# CarPC-CC-Var2.net
KiCad netlist of a schematic drawn in EAGLE
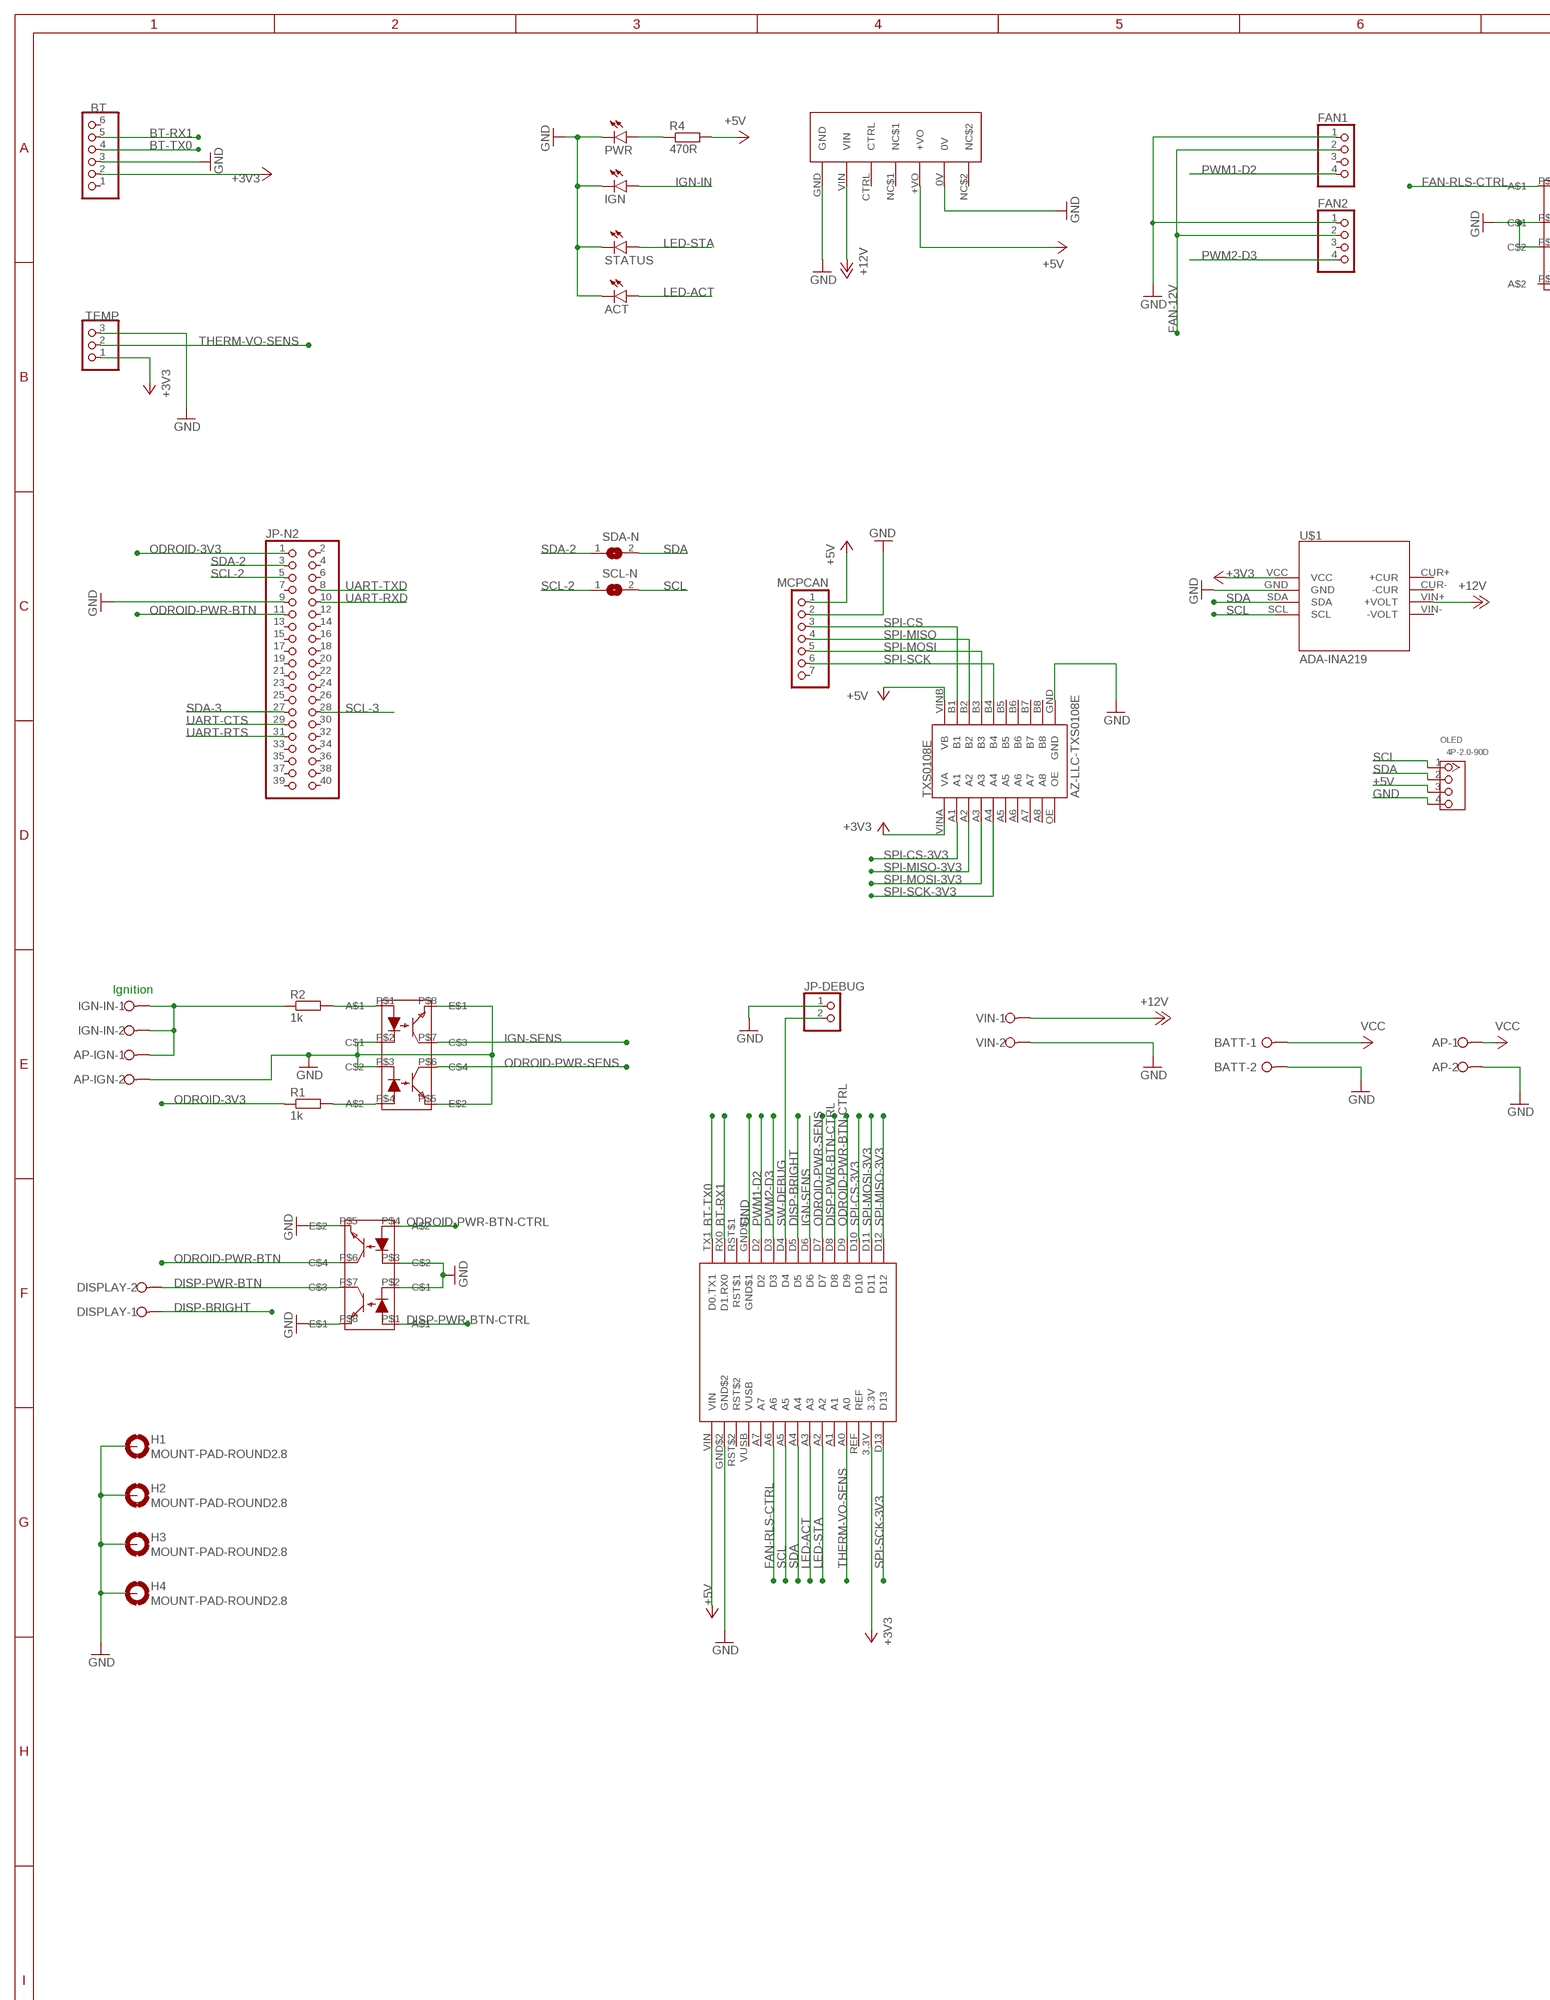
[diagram p0: schematic, sheet 1, part 1 of 2]
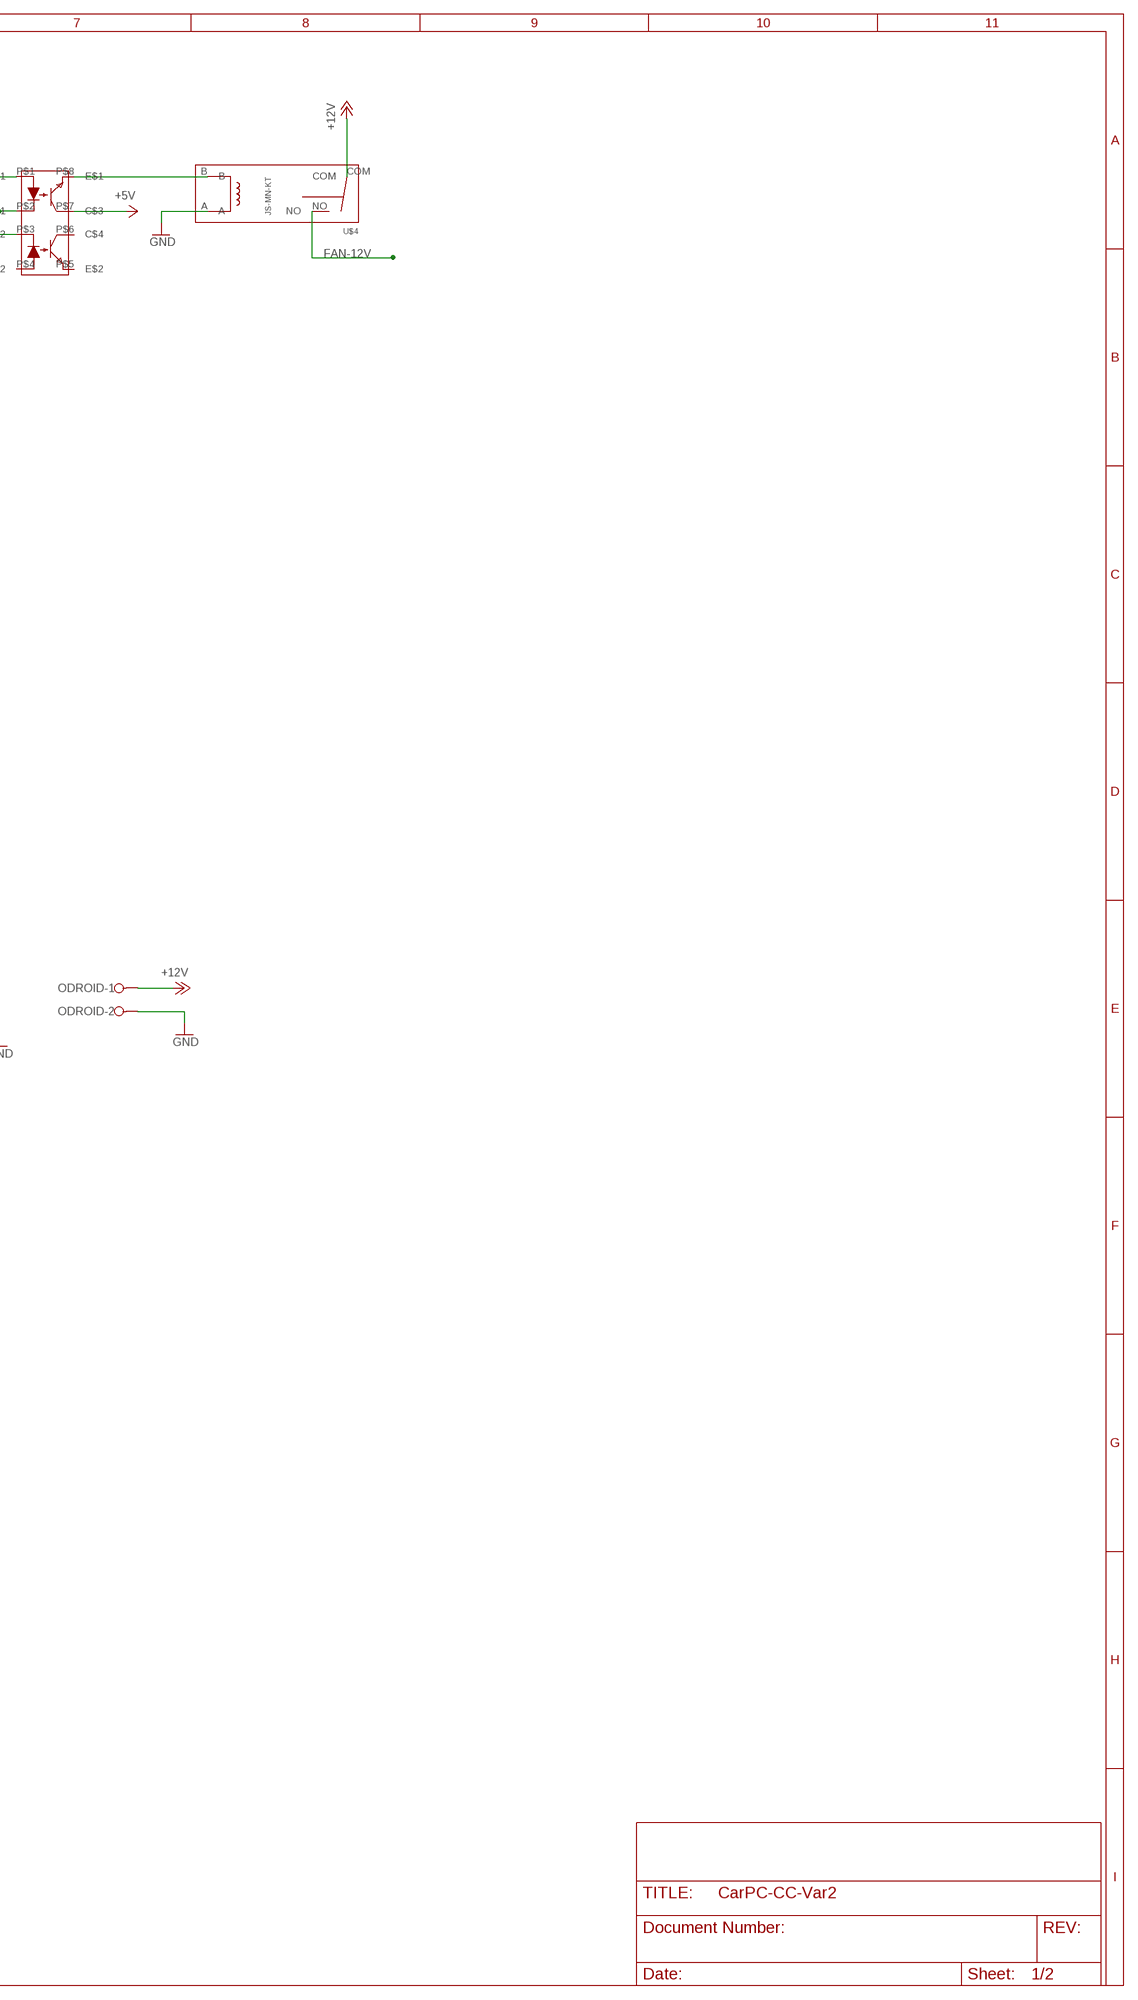
[diagram p1: schematic, sheet 1, part 2 of 2]

(export (version "E")
  (design (tool "Eeschema 10.0.6"))
  (components
    (comp (ref "ACT")
      (value "LED3MM")
      (footprint "eagle-import:LED3MM")
      (libsource (lib "eagle-import") (part "LED3MM"))
    )
    (comp (ref "AP")
      (value "W237-02P")
      (footprint "eagle-import:W237-132")
      (libsource (lib "eagle-import") (part "W237-02P"))
    )
    (comp (ref "AP-IGN")
      (value "W237-02P")
      (footprint "eagle-import:W237-132")
      (libsource (lib "eagle-import") (part "W237-02P"))
    )
    (comp (ref "ARD-NANO-33-IOT")
      (value "ARDUINONANO33IOT")
      (footprint "eagle-import:FPR_ARDNANO33IOT")
      (libsource (lib "eagle-import") (part "ARDUINONANO33IOT"))
    )
    (comp (ref "BATT")
      (value "W237-02P")
      (footprint "eagle-import:W237-132")
      (libsource (lib "eagle-import") (part "W237-02P"))
    )
    (comp (ref "BT")
      (value "PINHD-1X6/90")
      (footprint "eagle-import:1X06_90")
      (libsource (lib "eagle-import") (part "PINHD-1X6/90"))
    )
    (comp (ref "DISPLAY")
      (value "W237-02P")
      (footprint "eagle-import:W237-132")
      (libsource (lib "eagle-import") (part "W237-02P"))
    )
    (comp (ref "FAN1")
      (value "PINHD-1X4")
      (footprint "eagle-import:1X04")
      (libsource (lib "eagle-import") (part "PINHD-1X4"))
    )
    (comp (ref "FAN2")
      (value "PINHD-1X4")
      (footprint "eagle-import:1X04")
      (libsource (lib "eagle-import") (part "PINHD-1X4"))
    )
    (comp (ref "H1")
      (value "MOUNT-PAD-ROUND2.8")
      (footprint "eagle-import:2,8-PAD")
      (libsource (lib "eagle-import") (part "MOUNT-PAD-ROUND2.8"))
    )
    (comp (ref "H2")
      (value "MOUNT-PAD-ROUND2.8")
      (footprint "eagle-import:2,8-PAD")
      (libsource (lib "eagle-import") (part "MOUNT-PAD-ROUND2.8"))
    )
    (comp (ref "H3")
      (value "MOUNT-PAD-ROUND2.8")
      (footprint "eagle-import:2,8-PAD")
      (libsource (lib "eagle-import") (part "MOUNT-PAD-ROUND2.8"))
    )
    (comp (ref "H4")
      (value "MOUNT-PAD-ROUND2.8")
      (footprint "eagle-import:2,8-PAD")
      (libsource (lib "eagle-import") (part "MOUNT-PAD-ROUND2.8"))
    )
    (comp (ref "IGN")
      (value "LED3MM")
      (footprint "eagle-import:LED3MM")
      (libsource (lib "eagle-import") (part "LED3MM"))
    )
    (comp (ref "IGN-IN")
      (value "W237-02P")
      (footprint "eagle-import:W237-132")
      (libsource (lib "eagle-import") (part "W237-02P"))
    )
    (comp (ref "JP-DEBUG")
      (value "PINHD-1X2")
      (footprint "eagle-import:1X02")
      (libsource (lib "eagle-import") (part "PINHD-1X2"))
    )
    (comp (ref "JP-N2")
      (value "PINHD-2X20")
      (footprint "eagle-import:2X20")
      (libsource (lib "eagle-import") (part "PINHD-2X20"))
    )
    (comp (ref "MCPCAN")
      (value "PINHD-1X7/90")
      (footprint "eagle-import:1X07_90")
      (libsource (lib "eagle-import") (part "PINHD-1X7/90"))
    )
    (comp (ref "ODROID")
      (value "W237-02P")
      (footprint "eagle-import:W237-132")
      (libsource (lib "eagle-import") (part "W237-02P"))
    )
    (comp (ref "OK-FAN-CTRL")
      (value "ILD74")
      (footprint "eagle-import:FPR_ILD74")
      (libsource (lib "eagle-import") (part "ILD74"))
    )
    (comp (ref "OK-PWR-IGN")
      (value "ILD74")
      (footprint "eagle-import:FPR_ILD74")
      (libsource (lib "eagle-import") (part "ILD74"))
    )
    (comp (ref "OK-PWR-N2_DISP")
      (value "ILD74")
      (footprint "eagle-import:FPR_ILD74")
      (libsource (lib "eagle-import") (part "ILD74"))
    )
    (comp (ref "OLED")
      (value "4P-2.0-90D")
      (footprint "eagle-import:HW4-2.0-90D")
      (libsource (lib "eagle-import") (part "GROVE-CONNECTOR-DIP-90D(4P-2.0)"))
    )
    (comp (ref "PWR")
      (value "LED3MM")
      (footprint "eagle-import:LED3MM")
      (libsource (lib "eagle-import") (part "LED3MM"))
    )
    (comp (ref "R1")
      (value "1k")
      (footprint "eagle-import:0204_7")
      (libsource (lib "eagle-import") (part "R-EU_0204/7"))
    )
    (comp (ref "R2")
      (value "1k")
      (footprint "eagle-import:0204_7")
      (libsource (lib "eagle-import") (part "R-EU_0204/7"))
    )
    (comp (ref "R4")
      (value "470R")
      (footprint "eagle-import:0204_7")
      (libsource (lib "eagle-import") (part "R-EU_0204/7"))
    )
    (comp (ref "SCL-N")
      (value "SJ")
      (footprint "eagle-import:SJ")
      (libsource (lib "eagle-import") (part "SJ"))
    )
    (comp (ref "SDA-N")
      (value "SJ")
      (footprint "eagle-import:SJ")
      (libsource (lib "eagle-import") (part "SJ"))
    )
    (comp (ref "STATUS")
      (value "LED3MM")
      (footprint "eagle-import:LED3MM")
      (libsource (lib "eagle-import") (part "LED3MM"))
    )
    (comp (ref "TEMP")
      (value "PINHD-1X3/90")
      (footprint "eagle-import:1X03_90")
      (libsource (lib "eagle-import") (part "PINHD-1X3/90"))
    )
    (comp (ref "TXS0108E")
      (value "AZ-LLC-TXS0108E")
      (footprint "eagle-import:FPR_LLC")
      (libsource (lib "eagle-import") (part "AZ-LLC-TXS0108E"))
    )
    (comp (ref "U$1")
      (value "ADA-INA219")
      (footprint "eagle-import:FPR_INA219")
      (libsource (lib "eagle-import") (part "ADA-INA219"))
    )
    (comp (ref "U$3")
      (value "6S8W4_2405S1.6RP")
      (footprint "eagle-import:PAC_6S8W4_2405S1.6RP")
      (libsource (lib "eagle-import") (part "6S8W4_2405S1.6RP"))
    )
    (comp (ref "U$4")
      (value "JS-MN-KT")
      (footprint "eagle-import:FPR_JS-MN-KT")
      (libsource (lib "eagle-import") (part "JS-MN-KT"))
    )
    (comp (ref "VIN")
      (value "W237-02P")
      (footprint "eagle-import:W237-132")
      (libsource (lib "eagle-import") (part "W237-02P"))
    )
  )
  (nets
    (net (code "1") (name "+3V3") (class "Default")
      (node (ref "ARD-NANO-33-IOT") (pin "3.3V") (pinfunction "3.3V_3.3V") (pintype "bidirectional"))
      (node (ref "BT") (pin "2") (pinfunction "2_2") (pintype "passive"))
      (node (ref "TEMP") (pin "1") (pinfunction "1_1") (pintype "passive"))
      (node (ref "TXS0108E") (pin "VINA") (pinfunction "VA_VINA") (pintype "bidirectional"))
      (node (ref "U$1") (pin "VCC") (pinfunction "VCC_VCC") (pintype "bidirectional"))
    )
    (net (code "2") (name "+5V") (class "Default")
      (node (ref "ARD-NANO-33-IOT") (pin "VIN") (pinfunction "VIN_VIN") (pintype "bidirectional"))
      (node (ref "MCPCAN") (pin "1") (pinfunction "1_1") (pintype "passive"))
      (node (ref "OK-FAN-CTRL") (pin "P$7") (pinfunction "C$3_P$7") (pintype "bidirectional"))
      (node (ref "OLED") (pin "3") (pinfunction "3_3") (pintype "bidirectional"))
      (node (ref "R4") (pin "2") (pinfunction "2_2") (pintype "passive"))
      (node (ref "TXS0108E") (pin "VINB") (pinfunction "VB_VINB") (pintype "bidirectional"))
      (node (ref "U$3") (pin "+VO") (pinfunction "+VO_+VO") (pintype "output"))
    )
    (net (code "3") (name "+12V") (class "Default")
      (node (ref "ODROID") (pin "1") (pinfunction "KL_1") (pintype "passive"))
      (node (ref "U$1") (pin "VIN+") (pinfunction "+VOLT_VIN+") (pintype "bidirectional"))
      (node (ref "U$3") (pin "VIN") (pinfunction "VIN_VIN") (pintype "bidirectional"))
      (node (ref "U$4") (pin "COM") (pinfunction "COM_COM") (pintype "bidirectional"))
      (node (ref "VIN") (pin "1") (pinfunction "KL_1") (pintype "passive"))
    )
    (net (code "4") (name "BT-RX1") (class "Default")
      (node (ref "ARD-NANO-33-IOT") (pin "RX0") (pinfunction "D1.RX0_RX0") (pintype "bidirectional"))
      (node (ref "BT") (pin "5") (pinfunction "5_5") (pintype "passive"))
    )
    (net (code "5") (name "BT-TX0") (class "Default")
      (node (ref "ARD-NANO-33-IOT") (pin "TX1") (pinfunction "D0.TX1_TX1") (pintype "bidirectional"))
      (node (ref "BT") (pin "4") (pinfunction "4_4") (pintype "passive"))
    )
    (net (code "6") (name "DISP-BRIGHT") (class "Default")
      (node (ref "ARD-NANO-33-IOT") (pin "D5") (pinfunction "D5_D5") (pintype "bidirectional"))
      (node (ref "DISPLAY") (pin "1") (pinfunction "KL_1") (pintype "passive"))
    )
    (net (code "7") (name "DISP-PWR-BTN") (class "Default")
      (node (ref "DISPLAY") (pin "2") (pinfunction "KL_2") (pintype "passive"))
      (node (ref "OK-PWR-N2_DISP") (pin "P$7") (pinfunction "C$3_P$7") (pintype "bidirectional"))
    )
    (net (code "8") (name "DISP-PWR-BTN-CTRL") (class "Default")
      (node (ref "ARD-NANO-33-IOT") (pin "D8") (pinfunction "D8_D8") (pintype "bidirectional"))
      (node (ref "OK-PWR-N2_DISP") (pin "P$1") (pinfunction "A$1_P$1") (pintype "bidirectional"))
    )
    (net (code "9") (name "FAN-12V") (class "Default")
      (node (ref "FAN1") (pin "2") (pinfunction "2_2") (pintype "passive"))
      (node (ref "FAN2") (pin "2") (pinfunction "2_2") (pintype "passive"))
      (node (ref "U$4") (pin "NO") (pinfunction "NO_NO") (pintype "bidirectional"))
    )
    (net (code "10") (name "FAN-RLS-CTRL") (class "Default")
      (node (ref "ARD-NANO-33-IOT") (pin "A6") (pinfunction "A6_A6") (pintype "bidirectional"))
      (node (ref "OK-FAN-CTRL") (pin "P$1") (pinfunction "A$1_P$1") (pintype "bidirectional"))
    )
    (net (code "11") (name "GND") (class "Default")
      (node (ref "ACT") (pin "K") (pinfunction "C_K") (pintype "passive"))
      (node (ref "AP") (pin "2") (pinfunction "KL_2") (pintype "passive"))
      (node (ref "AP-IGN") (pin "2") (pinfunction "KL_2") (pintype "passive"))
      (node (ref "ARD-NANO-33-IOT") (pin "GND$1") (pinfunction "GND$1_GND$1") (pintype "bidirectional"))
      (node (ref "ARD-NANO-33-IOT") (pin "GND$2") (pinfunction "GND$2_GND$2") (pintype "bidirectional"))
      (node (ref "BATT") (pin "2") (pinfunction "KL_2") (pintype "passive"))
      (node (ref "BT") (pin "3") (pinfunction "3_3") (pintype "passive"))
      (node (ref "FAN1") (pin "1") (pinfunction "1_1") (pintype "passive"))
      (node (ref "FAN2") (pin "1") (pinfunction "1_1") (pintype "passive"))
      (node (ref "H1") (pin "B2,8") (pinfunction "MOUNT_B2,8") (pintype "passive"))
      (node (ref "H2") (pin "B2,8") (pinfunction "MOUNT_B2,8") (pintype "passive"))
      (node (ref "H3") (pin "B2,8") (pinfunction "MOUNT_B2,8") (pintype "passive"))
      (node (ref "H4") (pin "B2,8") (pinfunction "MOUNT_B2,8") (pintype "passive"))
      (node (ref "IGN") (pin "K") (pinfunction "C_K") (pintype "passive"))
      (node (ref "JP-DEBUG") (pin "1") (pinfunction "1_1") (pintype "passive"))
      (node (ref "JP-N2") (pin "9") (pinfunction "9_9") (pintype "passive"))
      (node (ref "MCPCAN") (pin "2") (pinfunction "2_2") (pintype "passive"))
      (node (ref "ODROID") (pin "2") (pinfunction "KL_2") (pintype "passive"))
      (node (ref "OK-FAN-CTRL") (pin "P$2") (pinfunction "C$1_P$2") (pintype "bidirectional"))
      (node (ref "OK-FAN-CTRL") (pin "P$3") (pinfunction "C$2_P$3") (pintype "bidirectional"))
      (node (ref "OK-PWR-IGN") (pin "P$2") (pinfunction "C$1_P$2") (pintype "bidirectional"))
      (node (ref "OK-PWR-IGN") (pin "P$3") (pinfunction "C$2_P$3") (pintype "bidirectional"))
      (node (ref "OK-PWR-IGN") (pin "P$5") (pinfunction "E$2_P$5") (pintype "bidirectional"))
      (node (ref "OK-PWR-IGN") (pin "P$8") (pinfunction "E$1_P$8") (pintype "bidirectional"))
      (node (ref "OK-PWR-N2_DISP") (pin "P$2") (pinfunction "C$1_P$2") (pintype "bidirectional"))
      (node (ref "OK-PWR-N2_DISP") (pin "P$3") (pinfunction "C$2_P$3") (pintype "bidirectional"))
      (node (ref "OK-PWR-N2_DISP") (pin "P$5") (pinfunction "E$2_P$5") (pintype "bidirectional"))
      (node (ref "OK-PWR-N2_DISP") (pin "P$8") (pinfunction "E$1_P$8") (pintype "bidirectional"))
      (node (ref "OLED") (pin "4") (pinfunction "4_4") (pintype "bidirectional"))
      (node (ref "PWR") (pin "K") (pinfunction "C_K") (pintype "passive"))
      (node (ref "STATUS") (pin "K") (pinfunction "C_K") (pintype "passive"))
      (node (ref "TEMP") (pin "3") (pinfunction "3_3") (pintype "passive"))
      (node (ref "TXS0108E") (pin "GND") (pinfunction "GND_GND") (pintype "bidirectional"))
      (node (ref "U$1") (pin "GND") (pinfunction "GND_GND") (pintype "bidirectional"))
      (node (ref "U$3") (pin "0V") (pinfunction "0V_0V") (pintype "bidirectional"))
      (node (ref "U$3") (pin "GND") (pinfunction "GND_GND") (pintype "input"))
      (node (ref "U$4") (pin "A") (pinfunction "A_A") (pintype "bidirectional"))
      (node (ref "VIN") (pin "2") (pinfunction "KL_2") (pintype "passive"))
    )
    (net (code "12") (name "IGN-IN") (class "Default")
      (node (ref "IGN") (pin "A") (pinfunction "A_A") (pintype "passive"))
      (node (ref "OK-PWR-IGN") (pin "P$1") (pinfunction "A$1_P$1") (pintype "bidirectional"))
      (node (ref "R2") (pin "2") (pinfunction "2_2") (pintype "passive"))
    )
    (net (code "13") (name "IGN-SENS") (class "Default")
      (node (ref "ARD-NANO-33-IOT") (pin "D6") (pinfunction "D6_D6") (pintype "bidirectional"))
      (node (ref "OK-PWR-IGN") (pin "P$7") (pinfunction "C$3_P$7") (pintype "bidirectional"))
    )
    (net (code "14") (name "LED-ACT") (class "Default")
      (node (ref "ACT") (pin "A") (pinfunction "A_A") (pintype "passive"))
      (node (ref "ARD-NANO-33-IOT") (pin "A3") (pinfunction "A3_A3") (pintype "bidirectional"))
    )
    (net (code "15") (name "LED-STA") (class "Default")
      (node (ref "ARD-NANO-33-IOT") (pin "A2") (pinfunction "A2_A2") (pintype "bidirectional"))
      (node (ref "STATUS") (pin "A") (pinfunction "A_A") (pintype "passive"))
    )
    (net (code "16") (name "Net-(AP-IGNA-KL)") (class "Default")
      (node (ref "AP-IGN") (pin "1") (pinfunction "KL_1") (pintype "passive"))
      (node (ref "IGN-IN") (pin "1") (pinfunction "KL_1") (pintype "passive"))
      (node (ref "IGN-IN") (pin "2") (pinfunction "KL_2") (pintype "passive"))
      (node (ref "R2") (pin "1") (pinfunction "1_1") (pintype "passive"))
    )
    (net (code "17") (name "Net-(OK-FAN-CTRL-E$1)") (class "Default")
      (node (ref "OK-FAN-CTRL") (pin "P$8") (pinfunction "E$1_P$8") (pintype "bidirectional"))
      (node (ref "U$4") (pin "B") (pinfunction "B_B") (pintype "bidirectional"))
    )
    (net (code "18") (name "Net-(OK-PWR-IGN-A$2)") (class "Default")
      (node (ref "OK-PWR-IGN") (pin "P$4") (pinfunction "A$2_P$4") (pintype "bidirectional"))
      (node (ref "R1") (pin "2") (pinfunction "2_2") (pintype "passive"))
    )
    (net (code "19") (name "Net-(PWR-PadA)") (class "Default")
      (node (ref "PWR") (pin "A") (pinfunction "A_A") (pintype "passive"))
      (node (ref "R4") (pin "1") (pinfunction "1_1") (pintype "passive"))
    )
    (net (code "20") (name "ODROID-3V3") (class "Default")
      (node (ref "JP-N2") (pin "1") (pinfunction "1_1") (pintype "passive"))
      (node (ref "R1") (pin "1") (pinfunction "1_1") (pintype "passive"))
    )
    (net (code "21") (name "ODROID-PWR-BTN") (class "Default")
      (node (ref "JP-N2") (pin "11") (pinfunction "11_11") (pintype "passive"))
      (node (ref "OK-PWR-N2_DISP") (pin "P$6") (pinfunction "C$4_P$6") (pintype "bidirectional"))
    )
    (net (code "22") (name "ODROID-PWR-BTN-CTRL") (class "Default")
      (node (ref "ARD-NANO-33-IOT") (pin "D9") (pinfunction "D9_D9") (pintype "bidirectional"))
      (node (ref "OK-PWR-N2_DISP") (pin "P$4") (pinfunction "A$2_P$4") (pintype "bidirectional"))
    )
    (net (code "23") (name "ODROID-PWR-SENS") (class "Default")
      (node (ref "ARD-NANO-33-IOT") (pin "D7") (pinfunction "D7_D7") (pintype "bidirectional"))
      (node (ref "OK-PWR-IGN") (pin "P$6") (pinfunction "C$4_P$6") (pintype "bidirectional"))
    )
    (net (code "24") (name "PWM1-D2") (class "Default")
      (node (ref "ARD-NANO-33-IOT") (pin "D2") (pinfunction "D2_D2") (pintype "bidirectional"))
      (node (ref "FAN1") (pin "4") (pinfunction "4_4") (pintype "passive"))
    )
    (net (code "25") (name "PWM2-D3") (class "Default")
      (node (ref "ARD-NANO-33-IOT") (pin "D3") (pinfunction "D3_D3") (pintype "bidirectional"))
      (node (ref "FAN2") (pin "4") (pinfunction "4_4") (pintype "passive"))
    )
    (net (code "26") (name "SCL") (class "Default")
      (node (ref "ARD-NANO-33-IOT") (pin "A5") (pinfunction "A5_A5") (pintype "bidirectional"))
      (node (ref "OLED") (pin "1") (pinfunction "1_1") (pintype "bidirectional"))
      (node (ref "SCL-N") (pin "2") (pinfunction "2_2") (pintype "passive"))
      (node (ref "U$1") (pin "SCL") (pinfunction "SCL_SCL") (pintype "bidirectional"))
    )
    (net (code "27") (name "SCL-2") (class "Default")
      (node (ref "JP-N2") (pin "5") (pinfunction "5_5") (pintype "passive"))
      (node (ref "SCL-N") (pin "1") (pinfunction "1_1") (pintype "passive"))
    )
    (net (code "28") (name "SCL-3") (class "Default")
      (node (ref "JP-N2") (pin "28") (pinfunction "28_28") (pintype "passive"))
    )
    (net (code "29") (name "SDA") (class "Default")
      (node (ref "ARD-NANO-33-IOT") (pin "A4") (pinfunction "A4_A4") (pintype "bidirectional"))
      (node (ref "OLED") (pin "2") (pinfunction "2_2") (pintype "bidirectional"))
      (node (ref "SDA-N") (pin "2") (pinfunction "2_2") (pintype "passive"))
      (node (ref "U$1") (pin "SDA") (pinfunction "SDA_SDA") (pintype "bidirectional"))
    )
    (net (code "30") (name "SDA-2") (class "Default")
      (node (ref "JP-N2") (pin "3") (pinfunction "3_3") (pintype "passive"))
      (node (ref "SDA-N") (pin "1") (pinfunction "1_1") (pintype "passive"))
    )
    (net (code "31") (name "SDA-3") (class "Default")
      (node (ref "JP-N2") (pin "27") (pinfunction "27_27") (pintype "passive"))
    )
    (net (code "32") (name "SPI-CS") (class "Default")
      (node (ref "MCPCAN") (pin "3") (pinfunction "3_3") (pintype "passive"))
      (node (ref "TXS0108E") (pin "B1") (pinfunction "B1_B1") (pintype "bidirectional"))
    )
    (net (code "33") (name "SPI-CS-3V3") (class "Default")
      (node (ref "ARD-NANO-33-IOT") (pin "D10") (pinfunction "D10_D10") (pintype "bidirectional"))
      (node (ref "TXS0108E") (pin "A1") (pinfunction "A1_A1") (pintype "bidirectional"))
    )
    (net (code "34") (name "SPI-MISO") (class "Default")
      (node (ref "MCPCAN") (pin "4") (pinfunction "4_4") (pintype "passive"))
      (node (ref "TXS0108E") (pin "B2") (pinfunction "B2_B2") (pintype "bidirectional"))
    )
    (net (code "35") (name "SPI-MISO-3V3") (class "Default")
      (node (ref "ARD-NANO-33-IOT") (pin "D12") (pinfunction "D12_D12") (pintype "bidirectional"))
      (node (ref "TXS0108E") (pin "A2") (pinfunction "A2_A2") (pintype "bidirectional"))
    )
    (net (code "36") (name "SPI-MOSI") (class "Default")
      (node (ref "MCPCAN") (pin "5") (pinfunction "5_5") (pintype "passive"))
      (node (ref "TXS0108E") (pin "B3") (pinfunction "B3_B3") (pintype "bidirectional"))
    )
    (net (code "37") (name "SPI-MOSI-3V3") (class "Default")
      (node (ref "ARD-NANO-33-IOT") (pin "D11") (pinfunction "D11_D11") (pintype "bidirectional"))
      (node (ref "TXS0108E") (pin "A3") (pinfunction "A3_A3") (pintype "bidirectional"))
    )
    (net (code "38") (name "SPI-SCK") (class "Default")
      (node (ref "MCPCAN") (pin "6") (pinfunction "6_6") (pintype "passive"))
      (node (ref "TXS0108E") (pin "B4") (pinfunction "B4_B4") (pintype "bidirectional"))
    )
    (net (code "39") (name "SPI-SCK-3V3") (class "Default")
      (node (ref "ARD-NANO-33-IOT") (pin "D13") (pinfunction "D13_D13") (pintype "bidirectional"))
      (node (ref "TXS0108E") (pin "A4") (pinfunction "A4_A4") (pintype "bidirectional"))
    )
    (net (code "40") (name "SW-DEBUG") (class "Default")
      (node (ref "ARD-NANO-33-IOT") (pin "D4") (pinfunction "D4_D4") (pintype "bidirectional"))
      (node (ref "JP-DEBUG") (pin "2") (pinfunction "2_2") (pintype "passive"))
    )
    (net (code "41") (name "THERM-VO-SENS") (class "Default")
      (node (ref "ARD-NANO-33-IOT") (pin "A0") (pinfunction "A0_A0") (pintype "bidirectional"))
      (node (ref "TEMP") (pin "2") (pinfunction "2_2") (pintype "passive"))
    )
    (net (code "42") (name "UART-CTS") (class "Default")
      (node (ref "JP-N2") (pin "29") (pinfunction "29_29") (pintype "passive"))
    )
    (net (code "43") (name "UART-RTS") (class "Default")
      (node (ref "JP-N2") (pin "31") (pinfunction "31_31") (pintype "passive"))
    )
    (net (code "44") (name "UART-RXD") (class "Default")
      (node (ref "JP-N2") (pin "10") (pinfunction "10_10") (pintype "passive"))
    )
    (net (code "45") (name "UART-TXD") (class "Default")
      (node (ref "JP-N2") (pin "8") (pinfunction "8_8") (pintype "passive"))
    )
    (net (code "46") (name "VCC") (class "Default")
      (node (ref "AP") (pin "1") (pinfunction "KL_1") (pintype "passive"))
      (node (ref "BATT") (pin "1") (pinfunction "KL_1") (pintype "passive"))
    )
    (net (code "47") (name "unconnected-(ARD-NANO-33-IOT-PadA1)") (class "Default")
      (node (ref "ARD-NANO-33-IOT") (pin "A1") (pinfunction "A1_A1") (pintype "bidirectional"))
    )
    (net (code "48") (name "unconnected-(ARD-NANO-33-IOT-PadA7)") (class "Default")
      (node (ref "ARD-NANO-33-IOT") (pin "A7") (pinfunction "A7_A7") (pintype "bidirectional"))
    )
    (net (code "49") (name "unconnected-(ARD-NANO-33-IOT-PadREF)") (class "Default")
      (node (ref "ARD-NANO-33-IOT") (pin "REF") (pinfunction "REF_REF") (pintype "bidirectional"))
    )
    (net (code "50") (name "unconnected-(ARD-NANO-33-IOT-PadRST$1)") (class "Default")
      (node (ref "ARD-NANO-33-IOT") (pin "RST$1") (pinfunction "RST$1_RST$1") (pintype "bidirectional"))
    )
    (net (code "51") (name "unconnected-(ARD-NANO-33-IOT-PadRST$2)") (class "Default")
      (node (ref "ARD-NANO-33-IOT") (pin "RST$2") (pinfunction "RST$2_RST$2") (pintype "bidirectional"))
    )
    (net (code "52") (name "unconnected-(ARD-NANO-33-IOT-PadVUSB)") (class "Default")
      (node (ref "ARD-NANO-33-IOT") (pin "VUSB") (pinfunction "VUSB_VUSB") (pintype "bidirectional"))
    )
    (net (code "53") (name "unconnected-(BT-Pad1)") (class "Default")
      (node (ref "BT") (pin "1") (pinfunction "1_1") (pintype "passive"))
    )
    (net (code "54") (name "unconnected-(BT-Pad6)") (class "Default")
      (node (ref "BT") (pin "6") (pinfunction "6_6") (pintype "passive"))
    )
    (net (code "55") (name "unconnected-(FAN1-Pad3)") (class "Default")
      (node (ref "FAN1") (pin "3") (pinfunction "3_3") (pintype "passive"))
    )
    (net (code "56") (name "unconnected-(FAN2-Pad3)") (class "Default")
      (node (ref "FAN2") (pin "3") (pinfunction "3_3") (pintype "passive"))
    )
    (net (code "57") (name "unconnected-(JP-N2-Pad2)") (class "Default")
      (node (ref "JP-N2") (pin "2") (pinfunction "2_2") (pintype "passive"))
    )
    (net (code "58") (name "unconnected-(JP-N2-Pad4)") (class "Default")
      (node (ref "JP-N2") (pin "4") (pinfunction "4_4") (pintype "passive"))
    )
    (net (code "59") (name "unconnected-(JP-N2-Pad6)") (class "Default")
      (node (ref "JP-N2") (pin "6") (pinfunction "6_6") (pintype "passive"))
    )
    (net (code "60") (name "unconnected-(JP-N2-Pad7)") (class "Default")
      (node (ref "JP-N2") (pin "7") (pinfunction "7_7") (pintype "passive"))
    )
    (net (code "61") (name "unconnected-(JP-N2-Pad12)") (class "Default")
      (node (ref "JP-N2") (pin "12") (pinfunction "12_12") (pintype "passive"))
    )
    (net (code "62") (name "unconnected-(JP-N2-Pad13)") (class "Default")
      (node (ref "JP-N2") (pin "13") (pinfunction "13_13") (pintype "passive"))
    )
    (net (code "63") (name "unconnected-(JP-N2-Pad14)") (class "Default")
      (node (ref "JP-N2") (pin "14") (pinfunction "14_14") (pintype "passive"))
    )
    (net (code "64") (name "unconnected-(JP-N2-Pad15)") (class "Default")
      (node (ref "JP-N2") (pin "15") (pinfunction "15_15") (pintype "passive"))
    )
    (net (code "65") (name "unconnected-(JP-N2-Pad16)") (class "Default")
      (node (ref "JP-N2") (pin "16") (pinfunction "16_16") (pintype "passive"))
    )
    (net (code "66") (name "unconnected-(JP-N2-Pad17)") (class "Default")
      (node (ref "JP-N2") (pin "17") (pinfunction "17_17") (pintype "passive"))
    )
    (net (code "67") (name "unconnected-(JP-N2-Pad18)") (class "Default")
      (node (ref "JP-N2") (pin "18") (pinfunction "18_18") (pintype "passive"))
    )
    (net (code "68") (name "unconnected-(JP-N2-Pad19)") (class "Default")
      (node (ref "JP-N2") (pin "19") (pinfunction "19_19") (pintype "passive"))
    )
    (net (code "69") (name "unconnected-(JP-N2-Pad20)") (class "Default")
      (node (ref "JP-N2") (pin "20") (pinfunction "20_20") (pintype "passive"))
    )
    (net (code "70") (name "unconnected-(JP-N2-Pad21)") (class "Default")
      (node (ref "JP-N2") (pin "21") (pinfunction "21_21") (pintype "passive"))
    )
    (net (code "71") (name "unconnected-(JP-N2-Pad22)") (class "Default")
      (node (ref "JP-N2") (pin "22") (pinfunction "22_22") (pintype "passive"))
    )
    (net (code "72") (name "unconnected-(JP-N2-Pad23)") (class "Default")
      (node (ref "JP-N2") (pin "23") (pinfunction "23_23") (pintype "passive"))
    )
    (net (code "73") (name "unconnected-(JP-N2-Pad24)") (class "Default")
      (node (ref "JP-N2") (pin "24") (pinfunction "24_24") (pintype "passive"))
    )
    (net (code "74") (name "unconnected-(JP-N2-Pad25)") (class "Default")
      (node (ref "JP-N2") (pin "25") (pinfunction "25_25") (pintype "passive"))
    )
    (net (code "75") (name "unconnected-(JP-N2-Pad26)") (class "Default")
      (node (ref "JP-N2") (pin "26") (pinfunction "26_26") (pintype "passive"))
    )
    (net (code "76") (name "unconnected-(JP-N2-Pad30)") (class "Default")
      (node (ref "JP-N2") (pin "30") (pinfunction "30_30") (pintype "passive"))
    )
    (net (code "77") (name "unconnected-(JP-N2-Pad32)") (class "Default")
      (node (ref "JP-N2") (pin "32") (pinfunction "32_32") (pintype "passive"))
    )
    (net (code "78") (name "unconnected-(JP-N2-Pad33)") (class "Default")
      (node (ref "JP-N2") (pin "33") (pinfunction "33_33") (pintype "passive"))
    )
    (net (code "79") (name "unconnected-(JP-N2-Pad34)") (class "Default")
      (node (ref "JP-N2") (pin "34") (pinfunction "34_34") (pintype "passive"))
    )
    (net (code "80") (name "unconnected-(JP-N2-Pad35)") (class "Default")
      (node (ref "JP-N2") (pin "35") (pinfunction "35_35") (pintype "passive"))
    )
    (net (code "81") (name "unconnected-(JP-N2-Pad36)") (class "Default")
      (node (ref "JP-N2") (pin "36") (pinfunction "36_36") (pintype "passive"))
    )
    (net (code "82") (name "unconnected-(JP-N2-Pad37)") (class "Default")
      (node (ref "JP-N2") (pin "37") (pinfunction "37_37") (pintype "passive"))
    )
    (net (code "83") (name "unconnected-(JP-N2-Pad38)") (class "Default")
      (node (ref "JP-N2") (pin "38") (pinfunction "38_38") (pintype "passive"))
    )
    (net (code "84") (name "unconnected-(JP-N2-Pad39)") (class "Default")
      (node (ref "JP-N2") (pin "39") (pinfunction "39_39") (pintype "passive"))
    )
    (net (code "85") (name "unconnected-(JP-N2-Pad40)") (class "Default")
      (node (ref "JP-N2") (pin "40") (pinfunction "40_40") (pintype "passive"))
    )
    (net (code "86") (name "unconnected-(MCPCAN-Pad7)") (class "Default")
      (node (ref "MCPCAN") (pin "7") (pinfunction "7_7") (pintype "passive"))
    )
    (net (code "87") (name "unconnected-(OK-FAN-CTRL-A$2-PadP$4)") (class "Default")
      (node (ref "OK-FAN-CTRL") (pin "P$4") (pinfunction "A$2_P$4") (pintype "bidirectional"))
    )
    (net (code "88") (name "unconnected-(OK-FAN-CTRL-C$4-PadP$6)") (class "Default")
      (node (ref "OK-FAN-CTRL") (pin "P$6") (pinfunction "C$4_P$6") (pintype "bidirectional"))
    )
    (net (code "89") (name "unconnected-(OK-FAN-CTRL-E$2-PadP$5)") (class "Default")
      (node (ref "OK-FAN-CTRL") (pin "P$5") (pinfunction "E$2_P$5") (pintype "bidirectional"))
    )
    (net (code "90") (name "unconnected-(TXS0108E-PadA5)") (class "Default")
      (node (ref "TXS0108E") (pin "A5") (pinfunction "A5_A5") (pintype "bidirectional"))
    )
    (net (code "91") (name "unconnected-(TXS0108E-PadA6)") (class "Default")
      (node (ref "TXS0108E") (pin "A6") (pinfunction "A6_A6") (pintype "bidirectional"))
    )
    (net (code "92") (name "unconnected-(TXS0108E-PadA7)") (class "Default")
      (node (ref "TXS0108E") (pin "A7") (pinfunction "A7_A7") (pintype "bidirectional"))
    )
    (net (code "93") (name "unconnected-(TXS0108E-PadA8)") (class "Default")
      (node (ref "TXS0108E") (pin "A8") (pinfunction "A8_A8") (pintype "bidirectional"))
    )
    (net (code "94") (name "unconnected-(TXS0108E-PadB5)") (class "Default")
      (node (ref "TXS0108E") (pin "B5") (pinfunction "B5_B5") (pintype "bidirectional"))
    )
    (net (code "95") (name "unconnected-(TXS0108E-PadB6)") (class "Default")
      (node (ref "TXS0108E") (pin "B6") (pinfunction "B6_B6") (pintype "bidirectional"))
    )
    (net (code "96") (name "unconnected-(TXS0108E-PadB7)") (class "Default")
      (node (ref "TXS0108E") (pin "B7") (pinfunction "B7_B7") (pintype "bidirectional"))
    )
    (net (code "97") (name "unconnected-(TXS0108E-PadB8)") (class "Default")
      (node (ref "TXS0108E") (pin "B8") (pinfunction "B8_B8") (pintype "bidirectional"))
    )
    (net (code "98") (name "unconnected-(TXS0108E-PadOE)") (class "Default")
      (node (ref "TXS0108E") (pin "OE") (pinfunction "OE_OE") (pintype "no_connect"))
    )
    (net (code "99") (name "unconnected-(U$1-+CUR-PadCUR+)") (class "Default")
      (node (ref "U$1") (pin "CUR+") (pinfunction "+CUR_CUR+") (pintype "bidirectional"))
    )
    (net (code "100") (name "unconnected-(U$1--CUR-PadCUR-)") (class "Default")
      (node (ref "U$1") (pin "CUR-") (pinfunction "-CUR_CUR-") (pintype "bidirectional"))
    )
    (net (code "101") (name "unconnected-(U$1--VOLT-PadVIN-)") (class "Default")
      (node (ref "U$1") (pin "VIN-") (pinfunction "-VOLT_VIN-") (pintype "bidirectional"))
    )
    (net (code "102") (name "unconnected-(U$3-PadCTRL)") (class "Default")
      (node (ref "U$3") (pin "CTRL") (pinfunction "CTRL_CTRL") (pintype "input"))
    )
    (net (code "103") (name "unconnected-(U$3-PadNC$1)") (class "Default")
      (node (ref "U$3") (pin "NC$1") (pinfunction "NC$1_NC$1") (pintype "no_connect"))
    )
    (net (code "104") (name "unconnected-(U$3-PadNC$2)") (class "Default")
      (node (ref "U$3") (pin "NC$2") (pinfunction "NC$2_NC$2") (pintype "no_connect"))
    )
  )
)
